# EVAL-CN0349-PMDZ-AltiumDesignerSchematic.net
KiCad netlist of a schematic drawn in Altium Designer
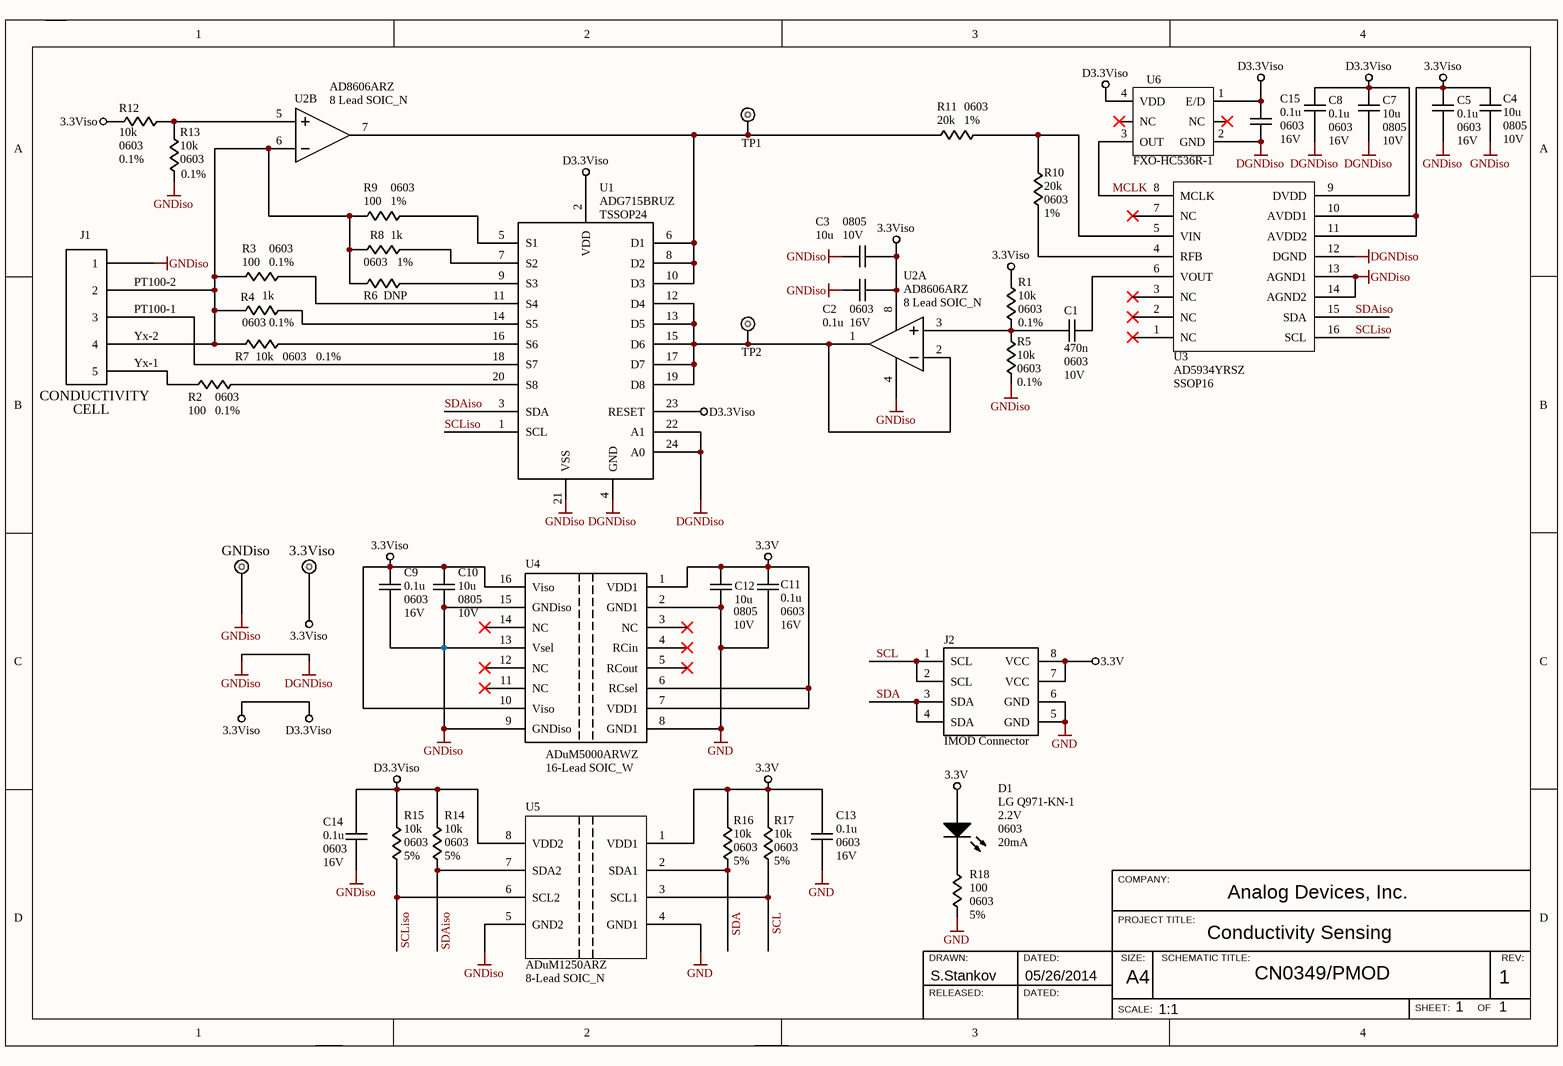
[diagram p0: EVAL-CN0349-PMDZ-AltiumDesignerSchematic-Rev0.SchDoc]

(export (version "E")
  (design (tool "Eeschema 10.0.6"))
  (components
    (comp (ref "3.3Viso")
      (value "TestPoint")
      (footprint "TestPoint")
      (libsource (lib "AnalogDevices") (part "TestPoint"))
    )
    (comp (ref "C1")
      (value "470n")
      (footprint "0603")
      (description "Capacitor")
      (fields (field (name "VOLTAGE") "10V") (field (name "Comment") "Cap"))
      (libsource (lib "AnalogDevices") (part "Cap"))
    )
    (comp (ref "C2")
      (value "0.1u")
      (footprint "0603")
      (description "Capacitor")
      (fields (field (name "VOLTAGE") "16V"))
      (libsource (lib "AnalogDevices") (part "Cap"))
    )
    (comp (ref "C3")
      (value "10u")
      (footprint "0805")
      (description "Capacitor")
      (fields (field (name "VOLTAGE") "10V"))
      (libsource (lib "AnalogDevices") (part "Cap"))
    )
    (comp (ref "C4")
      (value "10u")
      (footprint "0805")
      (description "Capacitor")
      (fields (field (name "VOLTAGE") "10V"))
      (libsource (lib "AnalogDevices") (part "Cap"))
    )
    (comp (ref "C5")
      (value "0.1u")
      (footprint "0603")
      (description "Capacitor")
      (fields (field (name "VOLTAGE") "16V"))
      (libsource (lib "AnalogDevices") (part "Cap"))
    )
    (comp (ref "C7")
      (value "10u")
      (footprint "0805")
      (description "Capacitor")
      (fields (field (name "VOLTAGE") "10V"))
      (libsource (lib "AnalogDevices") (part "Cap"))
    )
    (comp (ref "C8")
      (value "0.1u")
      (footprint "0603")
      (description "Capacitor")
      (fields (field (name "VOLTAGE") "16V"))
      (libsource (lib "AnalogDevices") (part "Cap"))
    )
    (comp (ref "C9")
      (value "0.1u")
      (footprint "0603")
      (description "Capacitor")
      (fields (field (name "VOLTAGE") "16V"))
      (libsource (lib "AnalogDevices") (part "Cap"))
    )
    (comp (ref "C10")
      (value "10u")
      (footprint "0805")
      (description "Capacitor")
      (fields (field (name "VOLTAGE") "10V"))
      (libsource (lib "AnalogDevices") (part "Cap"))
    )
    (comp (ref "C11")
      (value "0.1u")
      (footprint "0603")
      (description "Capacitor")
      (fields (field (name "VOLTAGE") "16V"))
      (libsource (lib "AnalogDevices") (part "Cap"))
    )
    (comp (ref "C12")
      (value "10u")
      (footprint "0805")
      (description "Capacitor")
      (fields (field (name "VOLTAGE") "10V"))
      (libsource (lib "AnalogDevices") (part "Cap"))
    )
    (comp (ref "C13")
      (value "0.1u")
      (footprint "0603")
      (description "Capacitor")
      (fields (field (name "VOLTAGE") "16V") (field (name "Comment") "Cap"))
      (libsource (lib "AnalogDevices") (part "Cap"))
    )
    (comp (ref "C14")
      (value "0.1u")
      (footprint "0603")
      (description "Capacitor")
      (fields (field (name "VOLTAGE") "16V") (field (name "Comment") "Cap"))
      (libsource (lib "AnalogDevices") (part "Cap"))
    )
    (comp (ref "C15")
      (value "0.1u")
      (footprint "0603")
      (description "Capacitor")
      (fields (field (name "VOLTAGE") "16V"))
      (libsource (lib "AnalogDevices") (part "Cap"))
    )
    (comp (ref "D1")
      (value "LG Q971-KN-1")
      (footprint "0603")
      (description "LED")
      (fields
        (field (name "DROP VOLTAGE") "2.2V")
        (field (name "CURRENT") "20mA")
        (field (name "Comment") "LED3")
      )
      (libsource (lib "AnalogDevices") (part "LED3"))
    )
    (comp (ref "GNDiso")
      (value "TestPoint")
      (footprint "TestPoint")
      (libsource (lib "AnalogDevices") (part "TestPoint"))
    )
    (comp (ref "J1")
      (value "J1")
      (footprint "Phoenix 5pin 2.54")
      (description "Connector 5pin")
      (fields (field (name "Comment") "CON5"))
      (libsource (lib "AnalogDevices") (part "CON5"))
    )
    (comp (ref "J2")
      (value "IMOD Connector")
      (footprint "IMOD Connector")
      (fields (field (name "Comment") "IMOD_8 PIN"))
      (libsource (lib "AnalogDevices") (part "IMOD_8 PIN"))
    )
    (comp (ref "R1")
      (value "10k")
      (footprint "0603 AD")
      (description "Resistor")
      (fields
        (field (name "FOOTRPRINT") "0603")
        (field (name "TOLERANCE") "0.1%")
        (field (name "Comment") "RESISTOR")
      )
      (libsource (lib "AnalogDevices") (part "RESISTOR"))
    )
    (comp (ref "R2")
      (value "100")
      (footprint "0603 AD")
      (description "Resistor")
      (fields
        (field (name "FOOTRPRINT") "0603")
        (field (name "TOLERANCE") "0.1%")
        (field (name "Comment") "RESISTOR")
      )
      (libsource (lib "AnalogDevices") (part "RESISTOR"))
    )
    (comp (ref "R3")
      (value "100")
      (footprint "0603 AD")
      (description "Resistor")
      (fields
        (field (name "FOOTRPRINT") "0603")
        (field (name "TOLERANCE") "0.1%")
        (field (name "Comment") "RESISTOR")
      )
      (libsource (lib "AnalogDevices") (part "RESISTOR"))
    )
    (comp (ref "R4")
      (value "1k")
      (footprint "0603 AD")
      (description "Resistor")
      (fields
        (field (name "FOOTRPRINT") "0603")
        (field (name "TOLERANCE") "0.1%")
        (field (name "Comment") "RESISTOR")
      )
      (libsource (lib "AnalogDevices") (part "RESISTOR"))
    )
    (comp (ref "R5")
      (value "10k")
      (footprint "0603 AD")
      (description "Resistor")
      (fields
        (field (name "FOOTRPRINT") "0603")
        (field (name "TOLERANCE") "0.1%")
        (field (name "Comment") "RESISTOR")
      )
      (libsource (lib "AnalogDevices") (part "RESISTOR"))
    )
    (comp (ref "R6")
      (value "DNP")
      (footprint "0603 AD")
      (description "Resistor")
      (fields (field (name "TOLERANCE") "1%") (field (name "Comment") "RESISTOR"))
      (libsource (lib "AnalogDevices") (part "RESISTOR"))
    )
    (comp (ref "R7")
      (value "10k")
      (footprint "0603 AD")
      (description "Resistor")
      (fields
        (field (name "FOOTRPRINT") "0603")
        (field (name "TOLERANCE") "0.1%")
        (field (name "Comment") "RESISTOR")
      )
      (libsource (lib "AnalogDevices") (part "RESISTOR"))
    )
    (comp (ref "R8")
      (value "1k")
      (footprint "0603 AD")
      (description "Resistor")
      (fields
        (field (name "FOOTRPRINT") "0603")
        (field (name "TOLERANCE") "1%")
        (field (name "Comment") "RESISTOR")
      )
      (libsource (lib "AnalogDevices") (part "RESISTOR"))
    )
    (comp (ref "R9")
      (value "100")
      (footprint "0603 AD")
      (description "Resistor")
      (fields
        (field (name "FOOTRPRINT") "0603")
        (field (name "TOLERANCE") "1%")
        (field (name "Comment") "RESISTOR")
      )
      (libsource (lib "AnalogDevices") (part "RESISTOR"))
    )
    (comp (ref "R10")
      (value "20k")
      (footprint "0603 AD")
      (description "Resistor")
      (fields
        (field (name "FOOTRPRINT") "0603")
        (field (name "TOLERANCE") "1%")
        (field (name "Comment") "RESISTOR")
      )
      (libsource (lib "AnalogDevices") (part "RESISTOR"))
    )
    (comp (ref "R11")
      (value "20k")
      (footprint "0603 AD")
      (description "Resistor")
      (fields
        (field (name "FOOTRPRINT") "0603")
        (field (name "TOLERANCE") "1%")
        (field (name "Comment") "RESISTOR")
      )
      (libsource (lib "AnalogDevices") (part "RESISTOR"))
    )
    (comp (ref "R12")
      (value "10k")
      (footprint "0603 AD")
      (description "Resistor")
      (fields
        (field (name "FOOTRPRINT") "0603")
        (field (name "TOLERANCE") "0.1%")
        (field (name "Comment") "RESISTOR")
      )
      (libsource (lib "AnalogDevices") (part "RESISTOR"))
    )
    (comp (ref "R13")
      (value "10k")
      (footprint "0603 AD")
      (description "Resistor")
      (fields
        (field (name "FOOTRPRINT") "0603")
        (field (name "TOLERANCE") "0.1%")
        (field (name "Comment") "RESISTOR")
      )
      (libsource (lib "AnalogDevices") (part "RESISTOR"))
    )
    (comp (ref "R14")
      (value "10k")
      (footprint "0603 AD")
      (description "Resistor")
      (fields
        (field (name "FOOTRPRINT") "0603")
        (field (name "TOLERANCE") "5%")
        (field (name "Comment") "RESISTOR")
      )
      (libsource (lib "AnalogDevices") (part "RESISTOR"))
    )
    (comp (ref "R15")
      (value "10k")
      (footprint "0603 AD")
      (description "Resistor")
      (fields
        (field (name "FOOTRPRINT") "0603")
        (field (name "TOLERANCE") "5%")
        (field (name "Comment") "RESISTOR")
      )
      (libsource (lib "AnalogDevices") (part "RESISTOR"))
    )
    (comp (ref "R16")
      (value "10k")
      (footprint "0603 AD")
      (description "Resistor")
      (fields
        (field (name "FOOTRPRINT") "0603")
        (field (name "TOLERANCE") "5%")
        (field (name "Comment") "RESISTOR")
      )
      (libsource (lib "AnalogDevices") (part "RESISTOR"))
    )
    (comp (ref "R17")
      (value "10k")
      (footprint "0603 AD")
      (description "Resistor")
      (fields
        (field (name "FOOTRPRINT") "0603")
        (field (name "TOLERANCE") "5%")
        (field (name "Comment") "RESISTOR")
      )
      (libsource (lib "AnalogDevices") (part "RESISTOR"))
    )
    (comp (ref "R18")
      (value "100")
      (footprint "0603 AD")
      (description "Resistor")
      (fields
        (field (name "FOOTRPRINT") "0603")
        (field (name "TOLERANCE") "5%")
        (field (name "Comment") "RESISTOR")
      )
      (libsource (lib "AnalogDevices") (part "RESISTOR"))
    )
    (comp (ref "TP1")
      (value "TestPoint")
      (footprint "TestPoint")
      (libsource (lib "AnalogDevices") (part "TestPoint"))
    )
    (comp (ref "TP2")
      (value "TestPoint")
      (footprint "TestPoint")
      (libsource (lib "AnalogDevices") (part "TestPoint"))
    )
    (comp (ref "U1")
      (value "ADG715BRUZ")
      (footprint "TSSOP24")
      (description "Integrated Switch")
      (fields (field (name "Comment") "ADG715"))
      (libsource (lib "AnalogDevices") (part "ADG715"))
    )
    (comp (ref "U2")
      (value "AD8606ARZ")
      (footprint "8 Lead SOIC_N")
      (description "Dual Operational Amplifier")
      (fields (field (name "Comment") "AD8606"))
      (libsource (lib "AnalogDevices") (part "AD8606"))
    )
    (comp (ref "U3")
      (value "AD5934YRSZ")
      (footprint "SSOP16")
      (description "Integrated Circuit")
      (libsource (lib "AnalogDevices") (part "AD5933"))
    )
    (comp (ref "U4")
      (value "ADuM5000ARWZ")
      (footprint "16-Lead SOIC_W")
      (description "Integrated Circuit")
      (libsource (lib "AnalogDevices") (part "ADuM5000"))
    )
    (comp (ref "U5")
      (value "ADuM1250ARZ")
      (footprint "8-Lead SOIC_N")
      (description "Integrated Circuit")
      (fields (field (name "Comment") "ADuM1251"))
      (libsource (lib "AnalogDevices") (part "ADuM1251"))
    )
    (comp (ref "U6")
      (value "SMD_OSCILLATOR")
      (footprint "Quad6")
      (description "FXO-HC536R-1")
      (libsource (lib "CN0349") (part "SMD_OSCILLATOR"))
    )
  )
  (nets
    (net (code "2") (name "/MCLK") (class "Default")
      (node (ref "U3") (pin "8") (pinfunction "MCLK_8") (pintype "passive"))
      (node (ref "U6") (pin "3") (pinfunction "OUT_3") (pintype "passive"))
    )
    (net (code "3") (name "/PT100-1") (class "Default")
      (node (ref "J1") (pin "3") (pinfunction "3_3") (pintype "passive"))
      (node (ref "U1") (pin "18") (pinfunction "S7_18") (pintype "passive"))
    )
    (net (code "4") (name "/PT100-2") (class "Default")
      (node (ref "J1") (pin "2") (pinfunction "2_2") (pintype "passive"))
      (node (ref "J1") (pin "4") (pinfunction "4_4") (pintype "passive"))
      (node (ref "R3") (pin "1") (pinfunction "1_1") (pintype "passive"))
      (node (ref "R4") (pin "1") (pinfunction "1_1") (pintype "passive"))
      (node (ref "R6") (pin "2") (pinfunction "2_2") (pintype "passive"))
      (node (ref "R7") (pin "1") (pinfunction "1_1") (pintype "passive"))
      (node (ref "R8") (pin "1") (pinfunction "1_1") (pintype "passive"))
      (node (ref "R9") (pin "1") (pinfunction "1_1") (pintype "passive"))
      (node (ref "U2") (pin "6") (pinfunction "-INB_6") (pintype "passive"))
    )
    (net (code "5") (name "/SCL") (class "Default")
      (node (ref "J2") (pin "1") (pinfunction "SCL_1") (pintype "passive"))
      (node (ref "J2") (pin "2") (pinfunction "SCL_2") (pintype "passive"))
      (node (ref "R17") (pin "1") (pinfunction "1_1") (pintype "passive"))
      (node (ref "U5") (pin "3") (pinfunction "SCL1_3") (pintype "passive"))
    )
    (net (code "6") (name "/SCLiso") (class "Default")
      (node (ref "R15") (pin "1") (pinfunction "1_1") (pintype "passive"))
      (node (ref "U1") (pin "1") (pinfunction "SCL_1") (pintype "passive"))
      (node (ref "U3") (pin "16") (pinfunction "SCL_16") (pintype "passive"))
      (node (ref "U5") (pin "6") (pinfunction "SCL2_6") (pintype "passive"))
    )
    (net (code "7") (name "/SDA") (class "Default")
      (node (ref "J2") (pin "3") (pinfunction "SDA_3") (pintype "passive"))
      (node (ref "J2") (pin "4") (pinfunction "SDA_4") (pintype "passive"))
      (node (ref "R16") (pin "1") (pinfunction "1_1") (pintype "passive"))
      (node (ref "U5") (pin "2") (pinfunction "SDA1_2") (pintype "passive"))
    )
    (net (code "8") (name "/SDAiso") (class "Default")
      (node (ref "R14") (pin "1") (pinfunction "1_1") (pintype "passive"))
      (node (ref "U1") (pin "3") (pinfunction "SDA_3") (pintype "passive"))
      (node (ref "U3") (pin "15") (pinfunction "SDA_15") (pintype "passive"))
      (node (ref "U5") (pin "7") (pinfunction "SDA2_7") (pintype "passive"))
    )
    (net (code "9") (name "/Yx-1") (class "Default")
      (node (ref "J1") (pin "5") (pinfunction "5_5") (pintype "passive"))
      (node (ref "R2") (pin "1") (pinfunction "1_1") (pintype "passive"))
    )
    (net (code "10") (name "3.3V") (class "Default")
      (node (ref "C11") (pin "1") (pinfunction "1_1") (pintype "passive"))
      (node (ref "C12") (pin "2") (pinfunction "2_2") (pintype "passive"))
      (node (ref "C13") (pin "2") (pinfunction "2_2") (pintype "passive"))
      (node (ref "D1") (pin "A") (pinfunction "A_A") (pintype "passive"))
      (node (ref "J2") (pin "7") (pinfunction "VCC_7") (pintype "passive"))
      (node (ref "J2") (pin "8") (pinfunction "VCC_8") (pintype "passive"))
      (node (ref "R16") (pin "2") (pinfunction "2_2") (pintype "passive"))
      (node (ref "R17") (pin "2") (pinfunction "2_2") (pintype "passive"))
      (node (ref "U4") (pin "1") (pinfunction "VDD1_1") (pintype "passive"))
      (node (ref "U4") (pin "6") (pinfunction "RCsel_6") (pintype "passive"))
      (node (ref "U4") (pin "7") (pinfunction "VDD1_7") (pintype "passive"))
      (node (ref "U5") (pin "1") (pinfunction "VDD1_1") (pintype "passive"))
    )
    (net (code "11") (name "3.3Viso") (class "Default")
      (node (ref "3.3Viso") (pin "1") (pinfunction "1_1") (pintype "passive"))
      (node (ref "C10") (pin "2") (pinfunction "2_2") (pintype "passive"))
      (node (ref "C14") (pin "2") (pinfunction "2_2") (pintype "passive"))
      (node (ref "C15") (pin "1") (pinfunction "1_1") (pintype "passive"))
      (node (ref "C2") (pin "2") (pinfunction "2_2") (pintype "passive"))
      (node (ref "C3") (pin "1") (pinfunction "1_1") (pintype "passive"))
      (node (ref "C4") (pin "2") (pinfunction "2_2") (pintype "passive"))
      (node (ref "C5") (pin "1") (pinfunction "1_1") (pintype "passive"))
      (node (ref "C7") (pin "2") (pinfunction "2_2") (pintype "passive"))
      (node (ref "C8") (pin "1") (pinfunction "1_1") (pintype "passive"))
      (node (ref "C9") (pin "1") (pinfunction "1_1") (pintype "passive"))
      (node (ref "R1") (pin "2") (pinfunction "2_2") (pintype "passive"))
      (node (ref "R12") (pin "2") (pinfunction "2_2") (pintype "passive"))
      (node (ref "R14") (pin "2") (pinfunction "2_2") (pintype "passive"))
      (node (ref "R15") (pin "2") (pinfunction "2_2") (pintype "passive"))
      (node (ref "U1") (pin "2") (pinfunction "VDD_2") (pintype "passive"))
      (node (ref "U1") (pin "23") (pinfunction "RESET_23") (pintype "passive"))
      (node (ref "U2") (pin "8") (pinfunction "V+_8") (pintype "power_in"))
      (node (ref "U3") (pin "10") (pinfunction "AVDD1_10") (pintype "passive"))
      (node (ref "U3") (pin "11") (pinfunction "AVDD2_11") (pintype "passive"))
      (node (ref "U3") (pin "9") (pinfunction "DVDD_9") (pintype "passive"))
      (node (ref "U4") (pin "10") (pinfunction "Viso_10") (pintype "passive"))
      (node (ref "U4") (pin "16") (pinfunction "Viso_16") (pintype "passive"))
      (node (ref "U5") (pin "8") (pinfunction "VDD2_8") (pintype "passive"))
      (node (ref "U6") (pin "1") (pinfunction "E/D_1") (pintype "passive"))
      (node (ref "U6") (pin "4") (pinfunction "VDD_4") (pintype "passive"))
    )
    (net (code "12") (name "DGNDiso") (class "Default")
      (node (ref "C10") (pin "1") (pinfunction "1_1") (pintype "passive"))
      (node (ref "C14") (pin "1") (pinfunction "1_1") (pintype "passive"))
      (node (ref "C15") (pin "2") (pinfunction "2_2") (pintype "passive"))
      (node (ref "C2") (pin "1") (pinfunction "1_1") (pintype "passive"))
      (node (ref "C3") (pin "2") (pinfunction "2_2") (pintype "passive"))
      (node (ref "C4") (pin "1") (pinfunction "1_1") (pintype "passive"))
      (node (ref "C5") (pin "2") (pinfunction "2_2") (pintype "passive"))
      (node (ref "C7") (pin "1") (pinfunction "1_1") (pintype "passive"))
      (node (ref "C8") (pin "2") (pinfunction "2_2") (pintype "passive"))
      (node (ref "C9") (pin "2") (pinfunction "2_2") (pintype "passive"))
      (node (ref "GNDiso") (pin "1") (pinfunction "1_1") (pintype "passive"))
      (node (ref "J1") (pin "1") (pinfunction "1_1") (pintype "passive"))
      (node (ref "R13") (pin "1") (pinfunction "1_1") (pintype "passive"))
      (node (ref "R5") (pin "1") (pinfunction "1_1") (pintype "passive"))
      (node (ref "U1") (pin "21") (pinfunction "VSS_21") (pintype "passive"))
      (node (ref "U1") (pin "22") (pinfunction "A1_22") (pintype "passive"))
      (node (ref "U1") (pin "24") (pinfunction "A0_24") (pintype "passive"))
      (node (ref "U1") (pin "4") (pinfunction "GND_4") (pintype "passive"))
      (node (ref "U2") (pin "4") (pinfunction "V-_4") (pintype "power_in"))
      (node (ref "U3") (pin "12") (pinfunction "DGND_12") (pintype "passive"))
      (node (ref "U3") (pin "13") (pinfunction "AGND1_13") (pintype "passive"))
      (node (ref "U3") (pin "14") (pinfunction "AGND2_14") (pintype "passive"))
      (node (ref "U4") (pin "13") (pinfunction "Vsel_13") (pintype "passive"))
      (node (ref "U4") (pin "15") (pinfunction "GNDiso_15") (pintype "passive"))
      (node (ref "U4") (pin "9") (pinfunction "GNDiso_9") (pintype "passive"))
      (node (ref "U5") (pin "5") (pinfunction "GND2_5") (pintype "passive"))
      (node (ref "U6") (pin "2") (pinfunction "GND_2") (pintype "passive"))
    )
    (net (code "13") (name "GND") (class "Default")
      (node (ref "C11") (pin "2") (pinfunction "2_2") (pintype "passive"))
      (node (ref "C12") (pin "1") (pinfunction "1_1") (pintype "passive"))
      (node (ref "C13") (pin "1") (pinfunction "1_1") (pintype "passive"))
      (node (ref "J2") (pin "5") (pinfunction "GND_5") (pintype "passive"))
      (node (ref "J2") (pin "6") (pinfunction "GND_6") (pintype "passive"))
      (node (ref "R18") (pin "1") (pinfunction "1_1") (pintype "passive"))
      (node (ref "U4") (pin "2") (pinfunction "GND1_2") (pintype "passive"))
      (node (ref "U4") (pin "8") (pinfunction "GND1_8") (pintype "passive"))
      (node (ref "U5") (pin "4") (pinfunction "GND1_4") (pintype "passive"))
    )
    (net (code "14") (name "Net-(D1-PadK)") (class "Default")
      (node (ref "D1") (pin "K") (pinfunction "K_K") (pintype "passive"))
      (node (ref "R18") (pin "2") (pinfunction "2_2") (pintype "passive"))
    )
    (net (code "15") (name "Net-(U1-D1)") (class "Default")
      (node (ref "R11") (pin "2") (pinfunction "2_2") (pintype "passive"))
      (node (ref "TP1") (pin "1") (pinfunction "1_1") (pintype "passive"))
      (node (ref "U1") (pin "10") (pinfunction "D3_10") (pintype "passive"))
      (node (ref "U1") (pin "6") (pinfunction "D1_6") (pintype "passive"))
      (node (ref "U1") (pin "8") (pinfunction "D2_8") (pintype "passive"))
      (node (ref "U2") (pin "7") (pinfunction "OUTB_7") (pintype "passive"))
    )
    (net (code "16") (name "Net-(U1-D4)") (class "Default")
      (node (ref "TP2") (pin "1") (pinfunction "1_1") (pintype "passive"))
      (node (ref "U1") (pin "12") (pinfunction "D4_12") (pintype "passive"))
      (node (ref "U1") (pin "13") (pinfunction "D5_13") (pintype "passive"))
      (node (ref "U1") (pin "15") (pinfunction "D6_15") (pintype "passive"))
      (node (ref "U1") (pin "17") (pinfunction "D7_17") (pintype "passive"))
      (node (ref "U1") (pin "19") (pinfunction "D8_19") (pintype "passive"))
      (node (ref "U2") (pin "1") (pinfunction "OUTA_1") (pintype "passive"))
      (node (ref "U2") (pin "2") (pinfunction "-INA_2") (pintype "passive"))
    )
    (net (code "17") (name "Net-(U1-S1)") (class "Default")
      (node (ref "R9") (pin "2") (pinfunction "2_2") (pintype "passive"))
      (node (ref "U1") (pin "5") (pinfunction "S1_5") (pintype "passive"))
    )
    (net (code "18") (name "Net-(U1-S2)") (class "Default")
      (node (ref "R8") (pin "2") (pinfunction "2_2") (pintype "passive"))
      (node (ref "U1") (pin "7") (pinfunction "S2_7") (pintype "passive"))
    )
    (net (code "19") (name "Net-(U1-S3)") (class "Default")
      (node (ref "R6") (pin "1") (pinfunction "1_1") (pintype "passive"))
      (node (ref "U1") (pin "9") (pinfunction "S3_9") (pintype "passive"))
    )
    (net (code "20") (name "Net-(U1-S4)") (class "Default")
      (node (ref "R3") (pin "2") (pinfunction "2_2") (pintype "passive"))
      (node (ref "U1") (pin "11") (pinfunction "S4_11") (pintype "passive"))
    )
    (net (code "21") (name "Net-(U1-S5)") (class "Default")
      (node (ref "R4") (pin "2") (pinfunction "2_2") (pintype "passive"))
      (node (ref "U1") (pin "14") (pinfunction "S5_14") (pintype "passive"))
    )
    (net (code "22") (name "Net-(U1-S6)") (class "Default")
      (node (ref "R7") (pin "2") (pinfunction "2_2") (pintype "passive"))
      (node (ref "U1") (pin "16") (pinfunction "S6_16") (pintype "passive"))
    )
    (net (code "23") (name "Net-(U1-S8)") (class "Default")
      (node (ref "R2") (pin "2") (pinfunction "2_2") (pintype "passive"))
      (node (ref "U1") (pin "20") (pinfunction "S8_20") (pintype "passive"))
    )
    (net (code "24") (name "Net-(U2A-+INA)") (class "Default")
      (node (ref "C1") (pin "2") (pinfunction "2_2") (pintype "passive"))
      (node (ref "R1") (pin "1") (pinfunction "1_1") (pintype "passive"))
      (node (ref "R5") (pin "2") (pinfunction "2_2") (pintype "passive"))
      (node (ref "U2") (pin "3") (pinfunction "+INA_3") (pintype "passive"))
    )
    (net (code "25") (name "Net-(U2B-+INB)") (class "Default")
      (node (ref "R12") (pin "1") (pinfunction "1_1") (pintype "passive"))
      (node (ref "R13") (pin "2") (pinfunction "2_2") (pintype "passive"))
      (node (ref "U2") (pin "5") (pinfunction "+INB_5") (pintype "passive"))
    )
    (net (code "26") (name "Net-(U3-RFB)") (class "Default")
      (node (ref "R10") (pin "2") (pinfunction "2_2") (pintype "passive"))
      (node (ref "U3") (pin "4") (pinfunction "RFB_4") (pintype "passive"))
    )
    (net (code "27") (name "Net-(U3-VIN)") (class "Default")
      (node (ref "R10") (pin "1") (pinfunction "1_1") (pintype "passive"))
      (node (ref "R11") (pin "1") (pinfunction "1_1") (pintype "passive"))
      (node (ref "U3") (pin "5") (pinfunction "VIN_5") (pintype "passive"))
    )
    (net (code "28") (name "Net-(U3-VOUT)") (class "Default")
      (node (ref "C1") (pin "1") (pinfunction "1_1") (pintype "passive"))
      (node (ref "U3") (pin "6") (pinfunction "VOUT_6") (pintype "passive"))
    )
    (net (code "29") (name "unconnected-(U3-NC-Pad1)") (class "Default")
      (node (ref "U3") (pin "1") (pinfunction "NC_1") (pintype "passive+no_connect"))
    )
    (net (code "30") (name "unconnected-(U3-NC-Pad2)") (class "Default")
      (node (ref "U3") (pin "2") (pinfunction "NC_2") (pintype "passive+no_connect"))
    )
    (net (code "31") (name "unconnected-(U3-NC-Pad3)") (class "Default")
      (node (ref "U3") (pin "3") (pinfunction "NC_3") (pintype "passive+no_connect"))
    )
    (net (code "32") (name "unconnected-(U3-NC-Pad7)") (class "Default")
      (node (ref "U3") (pin "7") (pinfunction "NC_7") (pintype "passive+no_connect"))
    )
    (net (code "33") (name "unconnected-(U4-NC-Pad3)") (class "Default")
      (node (ref "U4") (pin "3") (pinfunction "NC_3") (pintype "passive+no_connect"))
    )
    (net (code "34") (name "unconnected-(U4-NC-Pad11)") (class "Default")
      (node (ref "U4") (pin "11") (pinfunction "NC_11") (pintype "passive+no_connect"))
    )
    (net (code "35") (name "unconnected-(U4-NC-Pad12)") (class "Default")
      (node (ref "U4") (pin "12") (pinfunction "NC_12") (pintype "passive+no_connect"))
    )
    (net (code "36") (name "unconnected-(U4-NC-Pad14)") (class "Default")
      (node (ref "U4") (pin "14") (pinfunction "NC_14") (pintype "passive+no_connect"))
    )
    (net (code "37") (name "unconnected-(U4-RCin-Pad4)") (class "Default")
      (node (ref "U4") (pin "4") (pinfunction "RCin_4") (pintype "passive+no_connect"))
    )
    (net (code "38") (name "unconnected-(U4-RCout-Pad5)") (class "Default")
      (node (ref "U4") (pin "5") (pinfunction "RCout_5") (pintype "passive+no_connect"))
    )
    (net (code "39") (name "unconnected-(U6-NC-Pad)") (class "Default")
      (node (ref "U6") (pin "") (pinfunction "NC_") (pintype "passive+no_connect"))
    )
    (net (code "40") (name "unconnected-(U6-NC-Pad)_1") (class "Default")
      (node (ref "U6") (pin "") (pinfunction "NC_") (pintype "passive+no_connect"))
    )
  )
)
